# littlelights.net
KiCad netlist of a schematic drawn in EAGLE
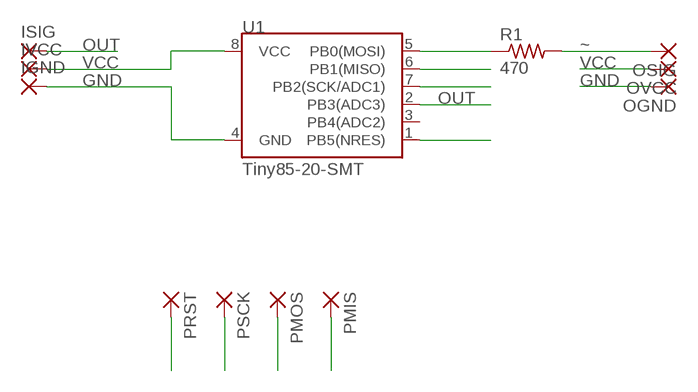
[diagram p0: schematic, sheet 1]

(export (version "E")
  (design (tool "Eeschema 10.0.6"))
  (components
    (comp (ref "IGND")
      (value "SMD2")
      (footprint "eagle-import:SMD1,27-2,54")
      (libsource (lib "eagle-import") (part "SMD2"))
    )
    (comp (ref "ISIG")
      (value "SMD2")
      (footprint "eagle-import:SMD1,27-2,54")
      (libsource (lib "eagle-import") (part "SMD2"))
    )
    (comp (ref "IVCC")
      (value "SMD2")
      (footprint "eagle-import:SMD1,27-2,54")
      (libsource (lib "eagle-import") (part "SMD2"))
    )
    (comp (ref "OGND")
      (value "SMD2")
      (footprint "eagle-import:SMD1,27-2,54")
      (libsource (lib "eagle-import") (part "SMD2"))
    )
    (comp (ref "OSIG")
      (value "SMD2")
      (footprint "eagle-import:SMD1,27-2,54")
      (libsource (lib "eagle-import") (part "SMD2"))
    )
    (comp (ref "OVCC")
      (value "SMD2")
      (footprint "eagle-import:SMD1,27-2,54")
      (libsource (lib "eagle-import") (part "SMD2"))
    )
    (comp (ref "PMIS")
      (value "SMD2")
      (footprint "eagle-import:SMD1,27-2,54")
      (libsource (lib "eagle-import") (part "SMD2"))
    )
    (comp (ref "PMOS")
      (value "SMD2")
      (footprint "eagle-import:SMD1,27-2,54")
      (libsource (lib "eagle-import") (part "SMD2"))
    )
    (comp (ref "PRST")
      (value "SMD2")
      (footprint "eagle-import:SMD1,27-2,54")
      (libsource (lib "eagle-import") (part "SMD2"))
    )
    (comp (ref "PSCK")
      (value "SMD2")
      (footprint "eagle-import:SMD1,27-2,54")
      (libsource (lib "eagle-import") (part "SMD2"))
    )
    (comp (ref "R1")
      (value "470")
      (footprint "eagle-import:R0603")
      (libsource (lib "eagle-import") (part "R-US_R0603"))
    )
    (comp (ref "U1")
      (value "Tiny85-20-SMT")
      (footprint "eagle-import:SO08-EIAJ")
      (libsource (lib "eagle-import") (part "ATTINY45TINY85-20-SMT"))
    )
  )
  (nets
    (net (code "1") (name "/GND") (class "Default")
      (node (ref "IGND") (pin "1") (pinfunction "P_1") (pintype "passive"))
      (node (ref "OGND") (pin "1") (pinfunction "P_1") (pintype "passive"))
      (node (ref "U1") (pin "4") (pinfunction "GND_4") (pintype "bidirectional"))
    )
    (net (code "2") (name "/MISO") (class "Default")
      (node (ref "PMIS") (pin "1") (pinfunction "P_1") (pintype "passive"))
      (node (ref "U1") (pin "6") (pinfunction "PB1(MISO)_6") (pintype "bidirectional"))
    )
    (net (code "3") (name "/MOSI") (class "Default")
      (node (ref "PMOS") (pin "1") (pinfunction "P_1") (pintype "passive"))
      (node (ref "R1") (pin "1") (pinfunction "1_1") (pintype "passive"))
      (node (ref "U1") (pin "5") (pinfunction "PB0(MOSI)_5") (pintype "bidirectional"))
    )
    (net (code "4") (name "/OUT") (class "Default")
      (node (ref "ISIG") (pin "1") (pinfunction "P_1") (pintype "passive"))
      (node (ref "U1") (pin "2") (pinfunction "PB3(ADC3)_2") (pintype "bidirectional"))
    )
    (net (code "5") (name "/RESET") (class "Default")
      (node (ref "PRST") (pin "1") (pinfunction "P_1") (pintype "passive"))
      (node (ref "U1") (pin "1") (pinfunction "PB5(NRES)_1") (pintype "bidirectional"))
    )
    (net (code "6") (name "/SCK") (class "Default")
      (node (ref "PSCK") (pin "1") (pinfunction "P_1") (pintype "passive"))
      (node (ref "U1") (pin "7") (pinfunction "PB2(SCK/ADC1)_7") (pintype "bidirectional"))
    )
    (net (code "7") (name "/VCC") (class "Default")
      (node (ref "IVCC") (pin "1") (pinfunction "P_1") (pintype "passive"))
      (node (ref "OVCC") (pin "1") (pinfunction "P_1") (pintype "passive"))
      (node (ref "U1") (pin "8") (pinfunction "VCC_8") (pintype "bidirectional"))
    )
    (net (code "8") (name "/~") (class "Default")
      (node (ref "OSIG") (pin "1") (pinfunction "P_1") (pintype "passive"))
      (node (ref "R1") (pin "2") (pinfunction "2_2") (pintype "passive"))
    )
    (net (code "9") (name "unconnected-(U1-PB4(ADC2)-Pad3)") (class "Default")
      (node (ref "U1") (pin "3") (pinfunction "PB4(ADC2)_3") (pintype "bidirectional"))
    )
  )
)
